# usb2ax_pro_top_TTL_v1_0.net
KiCad netlist of a schematic drawn in EAGLE
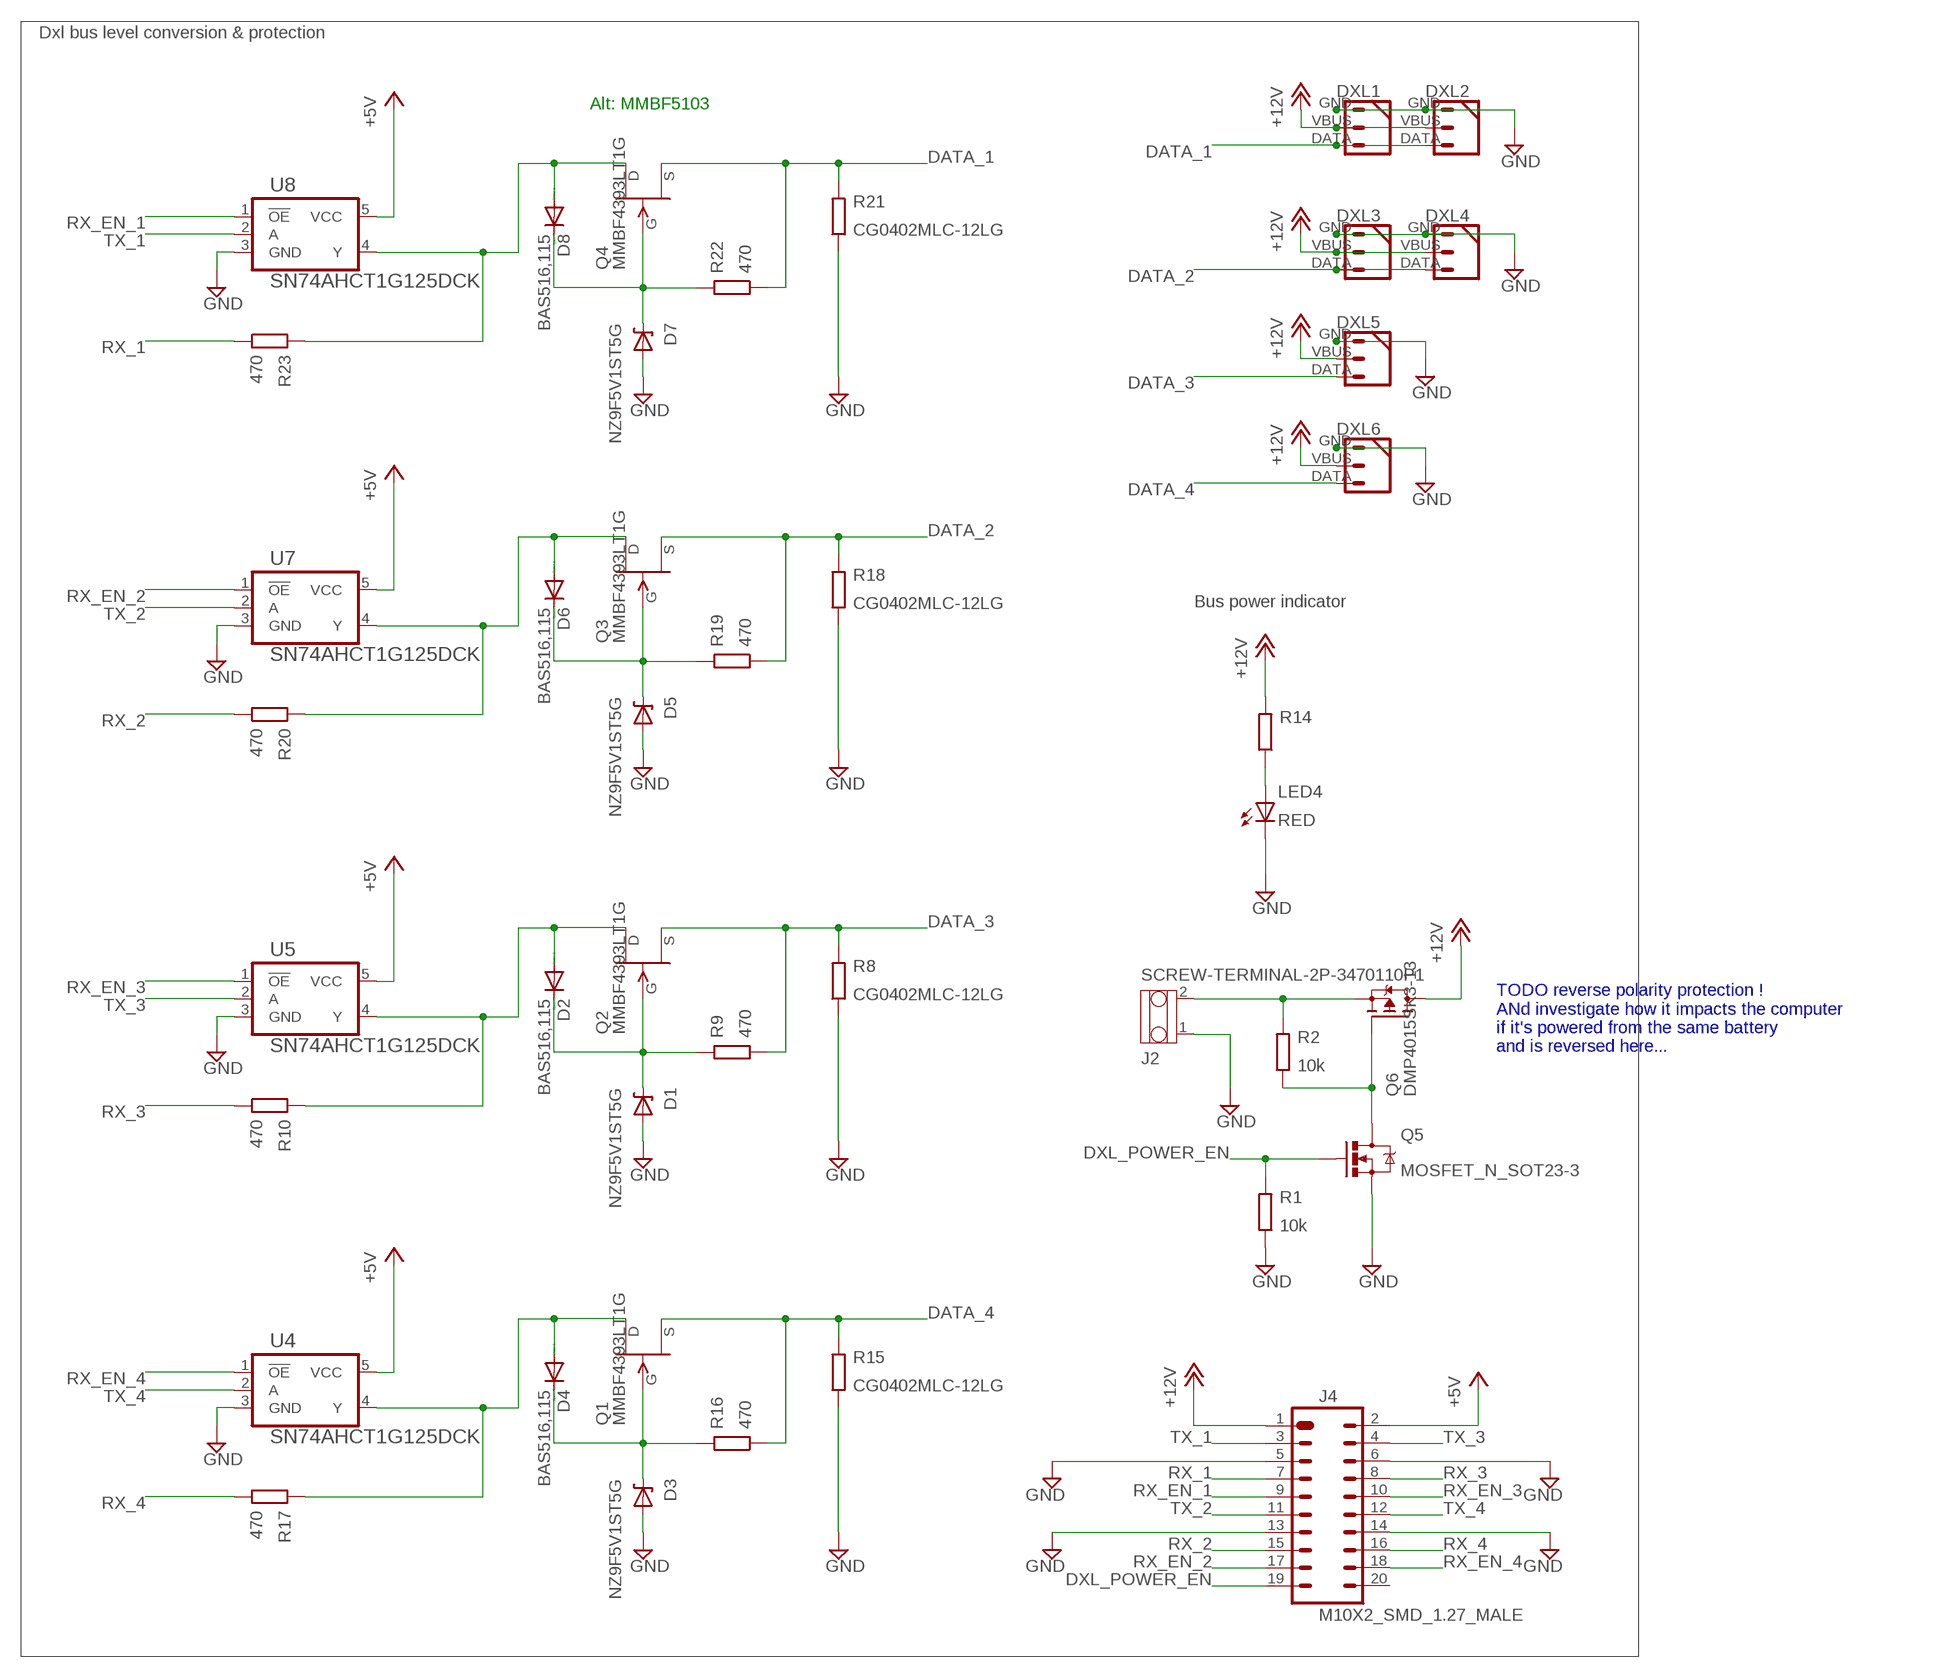
[diagram p0: schematic, sheet 1]

(export (version "E")
  (design (tool "Eeschema 10.0.6"))
  (components
    (comp (ref "D1")
      (value "NZ9F5V1ST5G")
      (footprint "eagle-import:SOD-923_N")
      (libsource (lib "eagle-import") (part "DIODE_ZENER-923"))
    )
    (comp (ref "D2")
      (value "BAS516,115")
      (footprint "eagle-import:SOD523")
      (libsource (lib "eagle-import") (part "DIODE-SOD523"))
    )
    (comp (ref "D3")
      (value "NZ9F5V1ST5G")
      (footprint "eagle-import:SOD-923_N")
      (libsource (lib "eagle-import") (part "DIODE_ZENER-923"))
    )
    (comp (ref "D4")
      (value "BAS516,115")
      (footprint "eagle-import:SOD523")
      (libsource (lib "eagle-import") (part "DIODE-SOD523"))
    )
    (comp (ref "D5")
      (value "NZ9F5V1ST5G")
      (footprint "eagle-import:SOD-923_N")
      (libsource (lib "eagle-import") (part "DIODE_ZENER-923"))
    )
    (comp (ref "D6")
      (value "BAS516,115")
      (footprint "eagle-import:SOD523")
      (libsource (lib "eagle-import") (part "DIODE-SOD523"))
    )
    (comp (ref "D7")
      (value "NZ9F5V1ST5G")
      (footprint "eagle-import:SOD-923_N")
      (libsource (lib "eagle-import") (part "DIODE_ZENER-923"))
    )
    (comp (ref "D8")
      (value "BAS516,115")
      (footprint "eagle-import:SOD523")
      (libsource (lib "eagle-import") (part "DIODE-SOD523"))
    )
    (comp (ref "DXL1")
      (value "DYNAMIXEL_3POS-R")
      (footprint "eagle-import:DYNAMIXEL_3POS_RIGHT")
      (libsource (lib "eagle-import") (part "DYNAMIXEL_3POS-R"))
    )
    (comp (ref "DXL2")
      (value "DYNAMIXEL_3POS-R")
      (footprint "eagle-import:DYNAMIXEL_3POS_RIGHT")
      (libsource (lib "eagle-import") (part "DYNAMIXEL_3POS-R"))
    )
    (comp (ref "DXL3")
      (value "DYNAMIXEL_3POS-R")
      (footprint "eagle-import:DYNAMIXEL_3POS_RIGHT")
      (libsource (lib "eagle-import") (part "DYNAMIXEL_3POS-R"))
    )
    (comp (ref "DXL4")
      (value "DYNAMIXEL_3POS-R")
      (footprint "eagle-import:DYNAMIXEL_3POS_RIGHT")
      (libsource (lib "eagle-import") (part "DYNAMIXEL_3POS-R"))
    )
    (comp (ref "DXL5")
      (value "DYNAMIXEL_3POS-R")
      (footprint "eagle-import:DYNAMIXEL_3POS_RIGHT")
      (libsource (lib "eagle-import") (part "DYNAMIXEL_3POS-R"))
    )
    (comp (ref "DXL6")
      (value "DYNAMIXEL_3POS-R")
      (footprint "eagle-import:DYNAMIXEL_3POS_RIGHT")
      (libsource (lib "eagle-import") (part "DYNAMIXEL_3POS-R"))
    )
    (comp (ref "J2")
      (value "SCREW-TERMINAL-2P-3470110P1")
      (footprint "eagle-import:2P-5.0")
      (libsource (lib "eagle-import") (part "SCREW-TERMINAL-2P-3470110P1"))
    )
    (comp (ref "J4")
      (value "M10X2_SMD_1.27_MALE")
      (footprint "eagle-import:2X10_SMD_1.27_MALE")
      (libsource (lib "eagle-import") (part "M10X2_SMD_1.27_MALE"))
    )
    (comp (ref "LED4")
      (value "RED")
      (footprint "eagle-import:D_0603_N")
      (libsource (lib "eagle-import") (part "LED0603"))
    )
    (comp (ref "Q1")
      (value "MMBF4393LT1G")
      (footprint "eagle-import:SOT-23-3_L_SSOT-3_L")
      (libsource (lib "eagle-import") (part "JFET_N_SOT-23-3_L"))
    )
    (comp (ref "Q2")
      (value "MMBF4393LT1G")
      (footprint "eagle-import:SOT-23-3_L_SSOT-3_L")
      (libsource (lib "eagle-import") (part "JFET_N_SOT-23-3_L"))
    )
    (comp (ref "Q3")
      (value "MMBF4393LT1G")
      (footprint "eagle-import:SOT-23-3_L_SSOT-3_L")
      (libsource (lib "eagle-import") (part "JFET_N_SOT-23-3_L"))
    )
    (comp (ref "Q4")
      (value "MMBF4393LT1G")
      (footprint "eagle-import:SOT-23-3_L_SSOT-3_L")
      (libsource (lib "eagle-import") (part "JFET_N_SOT-23-3_L"))
    )
    (comp (ref "Q5")
      (value "MOSFET_N_SOT23-3")
      (footprint "eagle-import:SOT-23-3_N_SSOT-3_N")
      (libsource (lib "eagle-import") (part "MOSFET_N_SOT23-3"))
    )
    (comp (ref "Q6")
      (value "DMP4015SK3-13")
      (footprint "eagle-import:TO252")
      (libsource (lib "eagle-import") (part "FDD4141TO252"))
    )
    (comp (ref "R1")
      (value "10k")
      (footprint "eagle-import:0402_N")
      (libsource (lib "eagle-import") (part "R0402"))
    )
    (comp (ref "R2")
      (value "10k")
      (footprint "eagle-import:0402_N")
      (libsource (lib "eagle-import") (part "R0402"))
    )
    (comp (ref "R8")
      (value "CG0402MLC-12LG")
      (footprint "eagle-import:0402_N")
      (libsource (lib "eagle-import") (part "R0402"))
    )
    (comp (ref "R9")
      (value "470")
      (footprint "eagle-import:0402_N")
      (libsource (lib "eagle-import") (part "R0402"))
    )
    (comp (ref "R10")
      (value "470")
      (footprint "eagle-import:0402_N")
      (libsource (lib "eagle-import") (part "R0402"))
    )
    (comp (ref "R14")
      (value "R0402")
      (footprint "eagle-import:0402_N")
      (libsource (lib "eagle-import") (part "R0402"))
    )
    (comp (ref "R15")
      (value "CG0402MLC-12LG")
      (footprint "eagle-import:0402_N")
      (libsource (lib "eagle-import") (part "R0402"))
    )
    (comp (ref "R16")
      (value "470")
      (footprint "eagle-import:0402_N")
      (libsource (lib "eagle-import") (part "R0402"))
    )
    (comp (ref "R17")
      (value "470")
      (footprint "eagle-import:0402_N")
      (libsource (lib "eagle-import") (part "R0402"))
    )
    (comp (ref "R18")
      (value "CG0402MLC-12LG")
      (footprint "eagle-import:0402_N")
      (libsource (lib "eagle-import") (part "R0402"))
    )
    (comp (ref "R19")
      (value "470")
      (footprint "eagle-import:0402_N")
      (libsource (lib "eagle-import") (part "R0402"))
    )
    (comp (ref "R20")
      (value "470")
      (footprint "eagle-import:0402_N")
      (libsource (lib "eagle-import") (part "R0402"))
    )
    (comp (ref "R21")
      (value "CG0402MLC-12LG")
      (footprint "eagle-import:0402_N")
      (libsource (lib "eagle-import") (part "R0402"))
    )
    (comp (ref "R22")
      (value "470")
      (footprint "eagle-import:0402_N")
      (libsource (lib "eagle-import") (part "R0402"))
    )
    (comp (ref "R23")
      (value "470")
      (footprint "eagle-import:0402_N")
      (libsource (lib "eagle-import") (part "R0402"))
    )
    (comp (ref "U4")
      (value "SN74AHCT1G125DCK")
      (footprint "eagle-import:SC70-5")
      (libsource (lib "eagle-import") (part "SN74AHCT1G125DCK"))
    )
    (comp (ref "U5")
      (value "SN74AHCT1G125DCK")
      (footprint "eagle-import:SC70-5")
      (libsource (lib "eagle-import") (part "SN74AHCT1G125DCK"))
    )
    (comp (ref "U7")
      (value "SN74AHCT1G125DCK")
      (footprint "eagle-import:SC70-5")
      (libsource (lib "eagle-import") (part "SN74AHCT1G125DCK"))
    )
    (comp (ref "U8")
      (value "SN74AHCT1G125DCK")
      (footprint "eagle-import:SC70-5")
      (libsource (lib "eagle-import") (part "SN74AHCT1G125DCK"))
    )
  )
  (nets
    (net (code "1") (name "+5V") (class "Default")
      (node (ref "J4") (pin "2") (pinfunction "2_2") (pintype "passive"))
      (node (ref "U4") (pin "5") (pinfunction "VCC_5") (pintype "power_in"))
      (node (ref "U5") (pin "5") (pinfunction "VCC_5") (pintype "power_in"))
      (node (ref "U7") (pin "5") (pinfunction "VCC_5") (pintype "power_in"))
      (node (ref "U8") (pin "5") (pinfunction "VCC_5") (pintype "power_in"))
    )
    (net (code "2") (name "+12V") (class "Default")
      (node (ref "DXL1") (pin "VBUS") (pinfunction "2_VBUS") (pintype "bidirectional"))
      (node (ref "DXL2") (pin "VBUS") (pinfunction "2_VBUS") (pintype "bidirectional"))
      (node (ref "DXL3") (pin "VBUS") (pinfunction "2_VBUS") (pintype "bidirectional"))
      (node (ref "DXL4") (pin "VBUS") (pinfunction "2_VBUS") (pintype "bidirectional"))
      (node (ref "DXL5") (pin "VBUS") (pinfunction "2_VBUS") (pintype "bidirectional"))
      (node (ref "DXL6") (pin "VBUS") (pinfunction "2_VBUS") (pintype "bidirectional"))
      (node (ref "J4") (pin "1") (pinfunction "1_1") (pintype "passive"))
      (node (ref "Q6") (pin "3") (pinfunction "D_3") (pintype "passive"))
      (node (ref "R14") (pin "2") (pinfunction "2_2") (pintype "passive"))
    )
    (net (code "3") (name "/DATA_1") (class "Default")
      (node (ref "DXL1") (pin "DATA") (pinfunction "3_DATA") (pintype "bidirectional"))
      (node (ref "DXL2") (pin "DATA") (pinfunction "3_DATA") (pintype "bidirectional"))
      (node (ref "Q4") (pin "2") (pinfunction "S_2") (pintype "passive"))
      (node (ref "R21") (pin "2") (pinfunction "2_2") (pintype "passive"))
      (node (ref "R22") (pin "1") (pinfunction "1_1") (pintype "passive"))
    )
    (net (code "4") (name "/DATA_2") (class "Default")
      (node (ref "DXL3") (pin "DATA") (pinfunction "3_DATA") (pintype "bidirectional"))
      (node (ref "DXL4") (pin "DATA") (pinfunction "3_DATA") (pintype "bidirectional"))
      (node (ref "Q3") (pin "2") (pinfunction "S_2") (pintype "passive"))
      (node (ref "R18") (pin "2") (pinfunction "2_2") (pintype "passive"))
      (node (ref "R19") (pin "1") (pinfunction "1_1") (pintype "passive"))
    )
    (net (code "5") (name "/DATA_3") (class "Default")
      (node (ref "DXL5") (pin "DATA") (pinfunction "3_DATA") (pintype "bidirectional"))
      (node (ref "Q2") (pin "2") (pinfunction "S_2") (pintype "passive"))
      (node (ref "R8") (pin "2") (pinfunction "2_2") (pintype "passive"))
      (node (ref "R9") (pin "1") (pinfunction "1_1") (pintype "passive"))
    )
    (net (code "6") (name "/DATA_4") (class "Default")
      (node (ref "DXL6") (pin "DATA") (pinfunction "3_DATA") (pintype "bidirectional"))
      (node (ref "Q1") (pin "2") (pinfunction "S_2") (pintype "passive"))
      (node (ref "R15") (pin "2") (pinfunction "2_2") (pintype "passive"))
      (node (ref "R16") (pin "1") (pinfunction "1_1") (pintype "passive"))
    )
    (net (code "7") (name "/DXL_POWER_EN") (class "Default")
      (node (ref "J4") (pin "19") (pinfunction "19_19") (pintype "passive"))
      (node (ref "Q5") (pin "1") (pinfunction "G_1") (pintype "passive"))
      (node (ref "R1") (pin "2") (pinfunction "2_2") (pintype "passive"))
    )
    (net (code "8") (name "/RX_1") (class "Default")
      (node (ref "J4") (pin "7") (pinfunction "7_7") (pintype "passive"))
      (node (ref "R23") (pin "1") (pinfunction "1_1") (pintype "passive"))
    )
    (net (code "9") (name "/RX_2") (class "Default")
      (node (ref "J4") (pin "15") (pinfunction "15_15") (pintype "passive"))
      (node (ref "R20") (pin "1") (pinfunction "1_1") (pintype "passive"))
    )
    (net (code "10") (name "/RX_3") (class "Default")
      (node (ref "J4") (pin "8") (pinfunction "8_8") (pintype "passive"))
      (node (ref "R10") (pin "1") (pinfunction "1_1") (pintype "passive"))
    )
    (net (code "11") (name "/RX_4") (class "Default")
      (node (ref "J4") (pin "16") (pinfunction "16_16") (pintype "passive"))
      (node (ref "R17") (pin "1") (pinfunction "1_1") (pintype "passive"))
    )
    (net (code "12") (name "/RX_EN_1") (class "Default")
      (node (ref "J4") (pin "9") (pinfunction "9_9") (pintype "passive"))
      (node (ref "U8") (pin "1") (pinfunction "~{OE}_1") (pintype "input"))
    )
    (net (code "13") (name "/RX_EN_2") (class "Default")
      (node (ref "J4") (pin "17") (pinfunction "17_17") (pintype "passive"))
      (node (ref "U7") (pin "1") (pinfunction "~{OE}_1") (pintype "input"))
    )
    (net (code "14") (name "/RX_EN_3") (class "Default")
      (node (ref "J4") (pin "10") (pinfunction "10_10") (pintype "passive"))
      (node (ref "U5") (pin "1") (pinfunction "~{OE}_1") (pintype "input"))
    )
    (net (code "15") (name "/RX_EN_4") (class "Default")
      (node (ref "J4") (pin "18") (pinfunction "18_18") (pintype "passive"))
      (node (ref "U4") (pin "1") (pinfunction "~{OE}_1") (pintype "input"))
    )
    (net (code "16") (name "/TX_1") (class "Default")
      (node (ref "J4") (pin "3") (pinfunction "3_3") (pintype "passive"))
      (node (ref "U8") (pin "2") (pinfunction "A_2") (pintype "input"))
    )
    (net (code "17") (name "/TX_2") (class "Default")
      (node (ref "J4") (pin "11") (pinfunction "11_11") (pintype "passive"))
      (node (ref "U7") (pin "2") (pinfunction "A_2") (pintype "input"))
    )
    (net (code "18") (name "/TX_3") (class "Default")
      (node (ref "J4") (pin "4") (pinfunction "4_4") (pintype "passive"))
      (node (ref "U5") (pin "2") (pinfunction "A_2") (pintype "input"))
    )
    (net (code "19") (name "/TX_4") (class "Default")
      (node (ref "J4") (pin "12") (pinfunction "12_12") (pintype "passive"))
      (node (ref "U4") (pin "2") (pinfunction "A_2") (pintype "input"))
    )
    (net (code "20") (name "GND") (class "Default")
      (node (ref "D1") (pin "A") (pinfunction "A_A") (pintype "passive"))
      (node (ref "D3") (pin "A") (pinfunction "A_A") (pintype "passive"))
      (node (ref "D5") (pin "A") (pinfunction "A_A") (pintype "passive"))
      (node (ref "D7") (pin "A") (pinfunction "A_A") (pintype "passive"))
      (node (ref "DXL1") (pin "GND") (pinfunction "1_GND") (pintype "bidirectional"))
      (node (ref "DXL2") (pin "GND") (pinfunction "1_GND") (pintype "bidirectional"))
      (node (ref "DXL3") (pin "GND") (pinfunction "1_GND") (pintype "bidirectional"))
      (node (ref "DXL4") (pin "GND") (pinfunction "1_GND") (pintype "bidirectional"))
      (node (ref "DXL5") (pin "GND") (pinfunction "1_GND") (pintype "bidirectional"))
      (node (ref "DXL6") (pin "GND") (pinfunction "1_GND") (pintype "bidirectional"))
      (node (ref "J2") (pin "1") (pinfunction "1_1") (pintype "bidirectional"))
      (node (ref "J4") (pin "13") (pinfunction "13_13") (pintype "passive"))
      (node (ref "J4") (pin "14") (pinfunction "14_14") (pintype "passive"))
      (node (ref "J4") (pin "5") (pinfunction "5_5") (pintype "passive"))
      (node (ref "J4") (pin "6") (pinfunction "6_6") (pintype "passive"))
      (node (ref "LED4") (pin "C") (pinfunction "C_C") (pintype "passive"))
      (node (ref "Q5") (pin "2") (pinfunction "S_2") (pintype "passive"))
      (node (ref "R1") (pin "1") (pinfunction "1_1") (pintype "passive"))
      (node (ref "R15") (pin "1") (pinfunction "1_1") (pintype "passive"))
      (node (ref "R18") (pin "1") (pinfunction "1_1") (pintype "passive"))
      (node (ref "R21") (pin "1") (pinfunction "1_1") (pintype "passive"))
      (node (ref "R8") (pin "1") (pinfunction "1_1") (pintype "passive"))
      (node (ref "U4") (pin "3") (pinfunction "GND_3") (pintype "power_in"))
      (node (ref "U5") (pin "3") (pinfunction "GND_3") (pintype "power_in"))
      (node (ref "U7") (pin "3") (pinfunction "GND_3") (pintype "power_in"))
      (node (ref "U8") (pin "3") (pinfunction "GND_3") (pintype "power_in"))
    )
    (net (code "21") (name "Net-(LED4-PadA)") (class "Default")
      (node (ref "LED4") (pin "A") (pinfunction "A_A") (pintype "passive"))
      (node (ref "R14") (pin "1") (pinfunction "1_1") (pintype "passive"))
    )
    (net (code "22") (name "Net-(Q1-D)") (class "Default")
      (node (ref "D4") (pin "A") (pinfunction "A_A") (pintype "passive"))
      (node (ref "Q1") (pin "1") (pinfunction "D_1") (pintype "passive"))
      (node (ref "R17") (pin "2") (pinfunction "2_2") (pintype "passive"))
      (node (ref "U4") (pin "4") (pinfunction "Y_4") (pintype "output"))
    )
    (net (code "23") (name "Net-(Q1-G)") (class "Default")
      (node (ref "D3") (pin "C") (pinfunction "C_C") (pintype "passive"))
      (node (ref "D4") (pin "C") (pinfunction "C_C") (pintype "passive"))
      (node (ref "Q1") (pin "3") (pinfunction "G_3") (pintype "passive"))
      (node (ref "R16") (pin "2") (pinfunction "2_2") (pintype "passive"))
    )
    (net (code "24") (name "Net-(Q2-D)") (class "Default")
      (node (ref "D2") (pin "A") (pinfunction "A_A") (pintype "passive"))
      (node (ref "Q2") (pin "1") (pinfunction "D_1") (pintype "passive"))
      (node (ref "R10") (pin "2") (pinfunction "2_2") (pintype "passive"))
      (node (ref "U5") (pin "4") (pinfunction "Y_4") (pintype "output"))
    )
    (net (code "25") (name "Net-(Q2-G)") (class "Default")
      (node (ref "D1") (pin "C") (pinfunction "C_C") (pintype "passive"))
      (node (ref "D2") (pin "C") (pinfunction "C_C") (pintype "passive"))
      (node (ref "Q2") (pin "3") (pinfunction "G_3") (pintype "passive"))
      (node (ref "R9") (pin "2") (pinfunction "2_2") (pintype "passive"))
    )
    (net (code "26") (name "Net-(Q3-D)") (class "Default")
      (node (ref "D6") (pin "A") (pinfunction "A_A") (pintype "passive"))
      (node (ref "Q3") (pin "1") (pinfunction "D_1") (pintype "passive"))
      (node (ref "R20") (pin "2") (pinfunction "2_2") (pintype "passive"))
      (node (ref "U7") (pin "4") (pinfunction "Y_4") (pintype "output"))
    )
    (net (code "27") (name "Net-(Q3-G)") (class "Default")
      (node (ref "D5") (pin "C") (pinfunction "C_C") (pintype "passive"))
      (node (ref "D6") (pin "C") (pinfunction "C_C") (pintype "passive"))
      (node (ref "Q3") (pin "3") (pinfunction "G_3") (pintype "passive"))
      (node (ref "R19") (pin "2") (pinfunction "2_2") (pintype "passive"))
    )
    (net (code "28") (name "Net-(Q4-D)") (class "Default")
      (node (ref "D8") (pin "A") (pinfunction "A_A") (pintype "passive"))
      (node (ref "Q4") (pin "1") (pinfunction "D_1") (pintype "passive"))
      (node (ref "R23") (pin "2") (pinfunction "2_2") (pintype "passive"))
      (node (ref "U8") (pin "4") (pinfunction "Y_4") (pintype "output"))
    )
    (net (code "29") (name "Net-(Q4-G)") (class "Default")
      (node (ref "D7") (pin "C") (pinfunction "C_C") (pintype "passive"))
      (node (ref "D8") (pin "C") (pinfunction "C_C") (pintype "passive"))
      (node (ref "Q4") (pin "3") (pinfunction "G_3") (pintype "passive"))
      (node (ref "R22") (pin "2") (pinfunction "2_2") (pintype "passive"))
    )
    (net (code "30") (name "Net-(Q5-D)") (class "Default")
      (node (ref "Q5") (pin "3") (pinfunction "D_3") (pintype "passive"))
      (node (ref "Q6") (pin "1") (pinfunction "G_1") (pintype "passive"))
      (node (ref "R2") (pin "1") (pinfunction "1_1") (pintype "passive"))
    )
    (net (code "31") (name "Net-(Q6-S)") (class "Default")
      (node (ref "J2") (pin "2") (pinfunction "2_2") (pintype "bidirectional"))
      (node (ref "Q6") (pin "2") (pinfunction "S_2") (pintype "passive"))
      (node (ref "R2") (pin "2") (pinfunction "2_2") (pintype "passive"))
    )
    (net (code "32") (name "unconnected-(J4-Pad20)") (class "Default")
      (node (ref "J4") (pin "20") (pinfunction "20_20") (pintype "passive"))
    )
  )
)
